# codec.net
KiCad netlist of a schematic drawn in Altium Designer
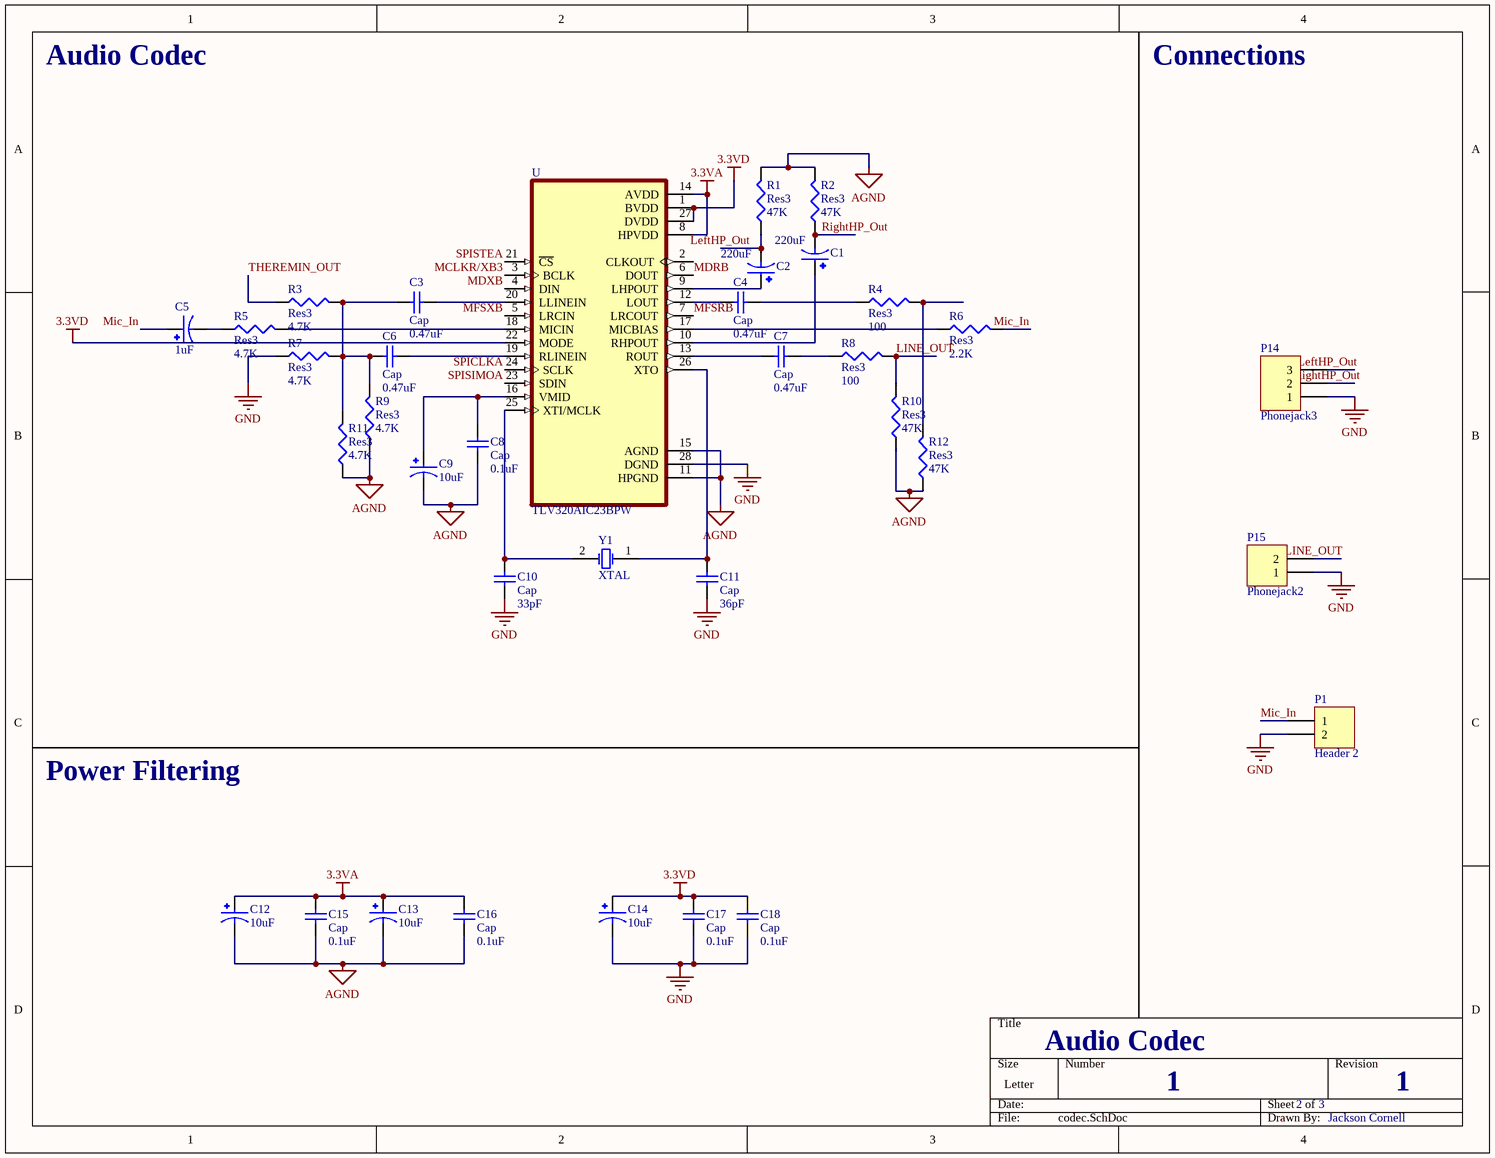
[diagram p0: codec.SchDoc]

(export (version "E")
  (design (tool "Eeschema 10.0.6"))
  (components
    (comp (ref "C1")
      (value "220uF")
      (footprint "CAPPRD500W60D1000H1250")
      (description "Aluminum Electrolytic Capacitors - Radial Leaded")
      (fields (field (name "MP") "EEU-FC1V221E") (field (name "MF") "Panasonic"))
      (libsource (lib "EEUFC1V221E") (part "EEUFC1V221E"))
    )
    (comp (ref "C2")
      (value "220uF")
      (footprint "CAPPRD500W60D1000H1250")
      (description "Aluminum Electrolytic Capacitors - Radial Leaded")
      (fields (field (name "MP") "EEU-FC1V221E") (field (name "MF") "Panasonic"))
      (libsource (lib "EEUFC1V221E") (part "EEUFC1V221E"))
    )
    (comp (ref "C3")
      (value "Cap")
      (footprint "Passives:CAPC0805")
      (description "Capacitor")
      (fields (field (name "ALTIUM_VALUE") "0.47uF") (field (name "PUBLISHER") "Altium Limited"))
      (libsource (lib "Miscellaneous Devices") (part "Cap"))
    )
    (comp (ref "C4")
      (value "Cap")
      (footprint "Passives:CAPC0805")
      (description "Capacitor")
      (fields (field (name "ALTIUM_VALUE") "0.47uF") (field (name "PUBLISHER") "Altium Limited"))
      (libsource (lib "Miscellaneous Devices") (part "Cap"))
    )
    (comp (ref "C5")
      (value "1uF")
      (footprint "CAPPRD500W60D1000H1250")
      (description "Aluminum Electrolytic Capacitors - Radial Leaded")
      (fields (field (name "MP") "EEU-FC1V221E") (field (name "MF") "Panasonic"))
      (libsource (lib "") (part "EEUFC1V221E_2"))
    )
    (comp (ref "C6")
      (value "Cap")
      (footprint "Passives:CAPC0805")
      (description "Capacitor")
      (fields (field (name "ALTIUM_VALUE") "0.47uF") (field (name "PUBLISHER") "Altium Limited"))
      (libsource (lib "Miscellaneous Devices") (part "Cap"))
    )
    (comp (ref "C7")
      (value "Cap")
      (footprint "Passives:CAPC0805")
      (description "Capacitor")
      (fields (field (name "ALTIUM_VALUE") "0.47uF") (field (name "PUBLISHER") "Altium Limited"))
      (libsource (lib "Miscellaneous Devices") (part "Cap"))
    )
    (comp (ref "C8")
      (value "Cap")
      (footprint "Passives:CAPC0805")
      (description "Capacitor")
      (fields (field (name "ALTIUM_VALUE") "0.1uF") (field (name "PUBLISHER") "Altium Limited"))
      (libsource (lib "Miscellaneous Devices") (part "Cap"))
    )
    (comp (ref "C9")
      (value "10uF")
      (footprint "CAPPRD500W60D1000H1250")
      (description "Aluminum Electrolytic Capacitors - Radial Leaded")
      (fields (field (name "MP") "EEU-FC1V221E") (field (name "MF") "Panasonic"))
      (libsource (lib "") (part "EEUFC1V221E_1"))
    )
    (comp (ref "C10")
      (value "Cap")
      (footprint "Passives:CAPC0805")
      (description "Capacitor")
      (fields (field (name "ALTIUM_VALUE") "33pF") (field (name "PUBLISHER") "Altium Limited"))
      (libsource (lib "Miscellaneous Devices") (part "Cap"))
    )
    (comp (ref "C11")
      (value "Cap")
      (footprint "Passives:CAPC0805")
      (description "Capacitor")
      (fields (field (name "ALTIUM_VALUE") "36pF") (field (name "PUBLISHER") "Altium Limited"))
      (libsource (lib "Miscellaneous Devices") (part "Cap"))
    )
    (comp (ref "C12")
      (value "10uF")
      (footprint "CAPPRD500W60D1000H1250")
      (description "Aluminum Electrolytic Capacitors - Radial Leaded")
      (fields (field (name "MP") "EEU-FC1V221E") (field (name "MF") "Panasonic"))
      (libsource (lib "") (part "EEUFC1V221E_1"))
    )
    (comp (ref "C13")
      (value "10uF")
      (footprint "CAPPRD500W60D1000H1250")
      (description "Aluminum Electrolytic Capacitors - Radial Leaded")
      (fields (field (name "MP") "EEU-FC1V221E") (field (name "MF") "Panasonic"))
      (libsource (lib "") (part "EEUFC1V221E_1"))
    )
    (comp (ref "C14")
      (value "10uF")
      (footprint "CAPPRD500W60D1000H1250")
      (description "Aluminum Electrolytic Capacitors - Radial Leaded")
      (fields (field (name "MP") "EEU-FC1V221E") (field (name "MF") "Panasonic"))
      (libsource (lib "") (part "EEUFC1V221E_1"))
    )
    (comp (ref "C15")
      (value "Cap")
      (footprint "Passives:CAPC0805")
      (description "Capacitor")
      (fields (field (name "ALTIUM_VALUE") "0.1uF") (field (name "PUBLISHER") "Altium Limited"))
      (libsource (lib "Miscellaneous Devices") (part "Cap"))
    )
    (comp (ref "C16")
      (value "Cap")
      (footprint "Passives:CAPC0805")
      (description "Capacitor")
      (fields (field (name "ALTIUM_VALUE") "0.1uF") (field (name "PUBLISHER") "Altium Limited"))
      (libsource (lib "Miscellaneous Devices") (part "Cap"))
    )
    (comp (ref "C17")
      (value "Cap")
      (footprint "Passives:CAPC0805")
      (description "Capacitor")
      (fields (field (name "ALTIUM_VALUE") "0.1uF") (field (name "PUBLISHER") "Altium Limited"))
      (libsource (lib "Miscellaneous Devices") (part "Cap"))
    )
    (comp (ref "C18")
      (value "Cap")
      (footprint "Passives:CAPC0805")
      (description "Capacitor")
      (fields (field (name "ALTIUM_VALUE") "0.1uF") (field (name "PUBLISHER") "Altium Limited"))
      (libsource (lib "Miscellaneous Devices") (part "Cap"))
    )
    (comp (ref "P1")
      (value "Header 2")
      (footprint "HDR1X2")
      (description "Header, 2-Pin")
      (fields (field (name "PUBLISHER") "Altium Limited"))
      (libsource (lib "Miscellaneous Connectors") (part "Header 2"))
    )
    (comp (ref "P14")
      (value "Phonejack3")
      (footprint "HDR1X3")
      (description "Header, 3-Pin")
      (fields (field (name "PUBLISHER") "Altium Limited"))
      (libsource (lib "Miscellaneous Connectors") (part "Header 3"))
    )
    (comp (ref "P15")
      (value "Phonejack2")
      (footprint "HDR1X2")
      (description "Header, 2-Pin")
      (fields (field (name "PUBLISHER") "Altium Limited"))
      (libsource (lib "") (part "Header 2_1"))
    )
    (comp (ref "R1")
      (value "Res3")
      (footprint "Passives:RES0805")
      (description "Resistor")
      (fields (field (name "ALTIUM_VALUE") "47K") (field (name "PUBLISHER") "Altium Limited"))
      (libsource (lib "Miscellaneous Devices") (part "Res3"))
    )
    (comp (ref "R2")
      (value "Res3")
      (footprint "Passives:RES0805")
      (description "Resistor")
      (fields (field (name "ALTIUM_VALUE") "47K") (field (name "PUBLISHER") "Altium Limited"))
      (libsource (lib "Miscellaneous Devices") (part "Res3"))
    )
    (comp (ref "R3")
      (value "Res3")
      (footprint "Passives:RES0805")
      (description "Resistor")
      (fields (field (name "ALTIUM_VALUE") "4.7K") (field (name "PUBLISHER") "Altium Limited"))
      (libsource (lib "Miscellaneous Devices") (part "Res3"))
    )
    (comp (ref "R4")
      (value "Res3")
      (footprint "Passives:RES0805")
      (description "Resistor")
      (fields (field (name "ALTIUM_VALUE") "100") (field (name "PUBLISHER") "Altium Limited"))
      (libsource (lib "Miscellaneous Devices") (part "Res3"))
    )
    (comp (ref "R5")
      (value "Res3")
      (footprint "Passives:RES0805")
      (description "Resistor")
      (fields (field (name "ALTIUM_VALUE") "4.7K") (field (name "PUBLISHER") "Altium Limited"))
      (libsource (lib "Miscellaneous Devices") (part "Res3"))
    )
    (comp (ref "R6")
      (value "Res3")
      (footprint "Passives:RES0805")
      (description "Resistor")
      (fields (field (name "ALTIUM_VALUE") "2.2K") (field (name "PUBLISHER") "Altium Limited"))
      (libsource (lib "Miscellaneous Devices") (part "Res3"))
    )
    (comp (ref "R7")
      (value "Res3")
      (footprint "Passives:RES0805")
      (description "Resistor")
      (fields (field (name "ALTIUM_VALUE") "4.7K") (field (name "PUBLISHER") "Altium Limited"))
      (libsource (lib "Miscellaneous Devices") (part "Res3"))
    )
    (comp (ref "R8")
      (value "Res3")
      (footprint "Passives:RES0805")
      (description "Resistor")
      (fields (field (name "ALTIUM_VALUE") "100") (field (name "PUBLISHER") "Altium Limited"))
      (libsource (lib "Miscellaneous Devices") (part "Res3"))
    )
    (comp (ref "R9")
      (value "Res3")
      (footprint "Passives:RES0805")
      (description "Resistor")
      (fields (field (name "ALTIUM_VALUE") "4.7K") (field (name "PUBLISHER") "Altium Limited"))
      (libsource (lib "Miscellaneous Devices") (part "Res3"))
    )
    (comp (ref "R10")
      (value "Res3")
      (footprint "Passives:RES0805")
      (description "Resistor")
      (fields (field (name "ALTIUM_VALUE") "47K") (field (name "PUBLISHER") "Altium Limited"))
      (libsource (lib "Miscellaneous Devices") (part "Res3"))
    )
    (comp (ref "R11")
      (value "Res3")
      (footprint "Passives:RES0805")
      (description "Resistor")
      (fields (field (name "ALTIUM_VALUE") "4.7K") (field (name "PUBLISHER") "Altium Limited"))
      (libsource (lib "Miscellaneous Devices") (part "Res3"))
    )
    (comp (ref "R12")
      (value "Res3")
      (footprint "Passives:RES0805")
      (description "Resistor")
      (fields (field (name "ALTIUM_VALUE") "47K") (field (name "PUBLISHER") "Altium Limited"))
      (libsource (lib "Miscellaneous Devices") (part "Res3"))
    )
    (comp (ref "U")
      (value "TLV320AIC23BPW")
      (footprint "SOP65P640X120-28N")
      (description "Low-Power Stereo CODEC with HP Amplifier 28-TSSOP -10 to 70")
      (fields (field (name "MF") "Texas Instruments"))
      (libsource (lib "TLV320AIC23BPW") (part "TLV320AIC23BPW"))
    )
    (comp (ref "Y1")
      (value "XTAL")
      (footprint "R38")
      (description "Crystal Oscillator")
      (fields (field (name "PUBLISHER") "Altium Limited"))
      (libsource (lib "Miscellaneous Devices") (part "XTAL"))
    )
  )
  (nets
    (net (code "1") (name "/LINE_OUT") (class "Default")
      (node (ref "P15") (pin "2") (pinfunction "2_2") (pintype "passive"))
      (node (ref "R10") (pin "2") (pinfunction "2_2") (pintype "passive"))
      (node (ref "R8") (pin "2") (pinfunction "2_2") (pintype "passive"))
    )
    (net (code "2") (name "/LeftHP_Out") (class "Default")
      (node (ref "C2") (pin "N") (pinfunction "N_N") (pintype "passive"))
      (node (ref "P14") (pin "3") (pinfunction "3_3") (pintype "passive"))
      (node (ref "R1") (pin "1") (pinfunction "1_1") (pintype "passive"))
    )
    (net (code "3") (name "/MCLKR{slash}XB3") (class "Default")
      (node (ref "U") (pin "3") (pinfunction "BCLK_3") (pintype "input"))
    )
    (net (code "4") (name "/MDRB") (class "Default")
      (node (ref "U") (pin "6") (pinfunction "DOUT_6") (pintype "output"))
    )
    (net (code "5") (name "/MDXB") (class "Default")
      (node (ref "U") (pin "4") (pinfunction "DIN_4") (pintype "input"))
    )
    (net (code "6") (name "/MFSRB") (class "Default")
      (node (ref "U") (pin "7") (pinfunction "LRCOUT_7") (pintype "output"))
    )
    (net (code "7") (name "/MFSXB") (class "Default")
      (node (ref "U") (pin "5") (pinfunction "LRCIN_5") (pintype "input"))
    )
    (net (code "8") (name "/Mic_In") (class "Default")
      (node (ref "C5") (pin "P") (pinfunction "P_P") (pintype "passive"))
      (node (ref "P1") (pin "1") (pinfunction "1_1") (pintype "passive"))
      (node (ref "R6") (pin "2") (pinfunction "2_2") (pintype "passive"))
    )
    (net (code "9") (name "/RightHP_Out") (class "Default")
      (node (ref "C1") (pin "N") (pinfunction "N_N") (pintype "passive"))
      (node (ref "P14") (pin "2") (pinfunction "2_2") (pintype "passive"))
      (node (ref "R2") (pin "1") (pinfunction "1_1") (pintype "passive"))
    )
    (net (code "10") (name "/SPICLKA") (class "Default")
      (node (ref "U") (pin "24") (pinfunction "SCLK_24") (pintype "input"))
    )
    (net (code "11") (name "/SPISIMOA") (class "Default")
      (node (ref "U") (pin "23") (pinfunction "SDIN_23") (pintype "input"))
    )
    (net (code "12") (name "/SPISTEA") (class "Default")
      (node (ref "U") (pin "21") (pinfunction "~{CS}_21") (pintype "input"))
    )
    (net (code "13") (name "/THEREMIN_OUT") (class "Default")
      (node (ref "R3") (pin "1") (pinfunction "1_1") (pintype "passive"))
    )
    (net (code "14") (name "3.3VA") (class "Default")
      (node (ref "C12") (pin "P") (pinfunction "P_P") (pintype "passive"))
      (node (ref "C13") (pin "P") (pinfunction "P_P") (pintype "passive"))
      (node (ref "C15") (pin "1") (pinfunction "1_1") (pintype "passive"))
      (node (ref "C16") (pin "1") (pinfunction "1_1") (pintype "passive"))
      (node (ref "U") (pin "14") (pinfunction "AVDD_14") (pintype "power_in"))
      (node (ref "U") (pin "8") (pinfunction "HPVDD_8") (pintype "power_in"))
    )
    (net (code "15") (name "3.3VD") (class "Default")
      (node (ref "C14") (pin "P") (pinfunction "P_P") (pintype "passive"))
      (node (ref "C17") (pin "2") (pinfunction "2_2") (pintype "passive"))
      (node (ref "C18") (pin "2") (pinfunction "2_2") (pintype "passive"))
      (node (ref "U") (pin "1") (pinfunction "BVDD_1") (pintype "power_in"))
      (node (ref "U") (pin "22") (pinfunction "MODE_22") (pintype "input"))
      (node (ref "U") (pin "27") (pinfunction "DVDD_27") (pintype "power_in"))
    )
    (net (code "16") (name "AGND") (class "Default")
      (node (ref "C12") (pin "N") (pinfunction "N_N") (pintype "passive"))
      (node (ref "C13") (pin "N") (pinfunction "N_N") (pintype "passive"))
      (node (ref "C15") (pin "2") (pinfunction "2_2") (pintype "passive"))
      (node (ref "C16") (pin "2") (pinfunction "2_2") (pintype "passive"))
      (node (ref "C8") (pin "1") (pinfunction "1_1") (pintype "passive"))
      (node (ref "C9") (pin "N") (pinfunction "N_N") (pintype "passive"))
      (node (ref "R1") (pin "2") (pinfunction "2_2") (pintype "passive"))
      (node (ref "R10") (pin "1") (pinfunction "1_1") (pintype "passive"))
      (node (ref "R11") (pin "1") (pinfunction "1_1") (pintype "passive"))
      (node (ref "R12") (pin "1") (pinfunction "1_1") (pintype "passive"))
      (node (ref "R2") (pin "2") (pinfunction "2_2") (pintype "passive"))
      (node (ref "R9") (pin "1") (pinfunction "1_1") (pintype "passive"))
      (node (ref "U") (pin "11") (pinfunction "HPGND_11") (pintype "power_in"))
      (node (ref "U") (pin "15") (pinfunction "AGND_15") (pintype "power_in"))
    )
    (net (code "17") (name "GND") (class "Default")
      (node (ref "C10") (pin "2") (pinfunction "2_2") (pintype "passive"))
      (node (ref "C11") (pin "2") (pinfunction "2_2") (pintype "passive"))
      (node (ref "C14") (pin "N") (pinfunction "N_N") (pintype "passive"))
      (node (ref "C17") (pin "1") (pinfunction "1_1") (pintype "passive"))
      (node (ref "C18") (pin "1") (pinfunction "1_1") (pintype "passive"))
      (node (ref "P1") (pin "2") (pinfunction "2_2") (pintype "passive"))
      (node (ref "P14") (pin "1") (pinfunction "1_1") (pintype "passive"))
      (node (ref "P15") (pin "1") (pinfunction "1_1") (pintype "passive"))
      (node (ref "R7") (pin "1") (pinfunction "1_1") (pintype "passive"))
      (node (ref "U") (pin "28") (pinfunction "DGND_28") (pintype "power_in"))
    )
    (net (code "18") (name "Net-(C3-Pad1)") (class "Default")
      (node (ref "C3") (pin "1") (pinfunction "1_1") (pintype "passive"))
      (node (ref "C6") (pin "1") (pinfunction "1_1") (pintype "passive"))
      (node (ref "R11") (pin "2") (pinfunction "2_2") (pintype "passive"))
      (node (ref "R3") (pin "2") (pinfunction "2_2") (pintype "passive"))
      (node (ref "R7") (pin "2") (pinfunction "2_2") (pintype "passive"))
      (node (ref "R9") (pin "2") (pinfunction "2_2") (pintype "passive"))
    )
    (net (code "19") (name "Net-(C4-Pad2)") (class "Default")
      (node (ref "C4") (pin "2") (pinfunction "2_2") (pintype "passive"))
      (node (ref "R4") (pin "1") (pinfunction "1_1") (pintype "passive"))
    )
    (net (code "20") (name "Net-(C5-PadN)") (class "Default")
      (node (ref "C5") (pin "N") (pinfunction "N_N") (pintype "passive"))
      (node (ref "R5") (pin "1") (pinfunction "1_1") (pintype "passive"))
    )
    (net (code "21") (name "Net-(C7-Pad2)") (class "Default")
      (node (ref "C7") (pin "2") (pinfunction "2_2") (pintype "passive"))
      (node (ref "R8") (pin "1") (pinfunction "1_1") (pintype "passive"))
    )
    (net (code "22") (name "Net-(R12-Pad2)") (class "Default")
      (node (ref "R12") (pin "2") (pinfunction "2_2") (pintype "passive"))
      (node (ref "R4") (pin "2") (pinfunction "2_2") (pintype "passive"))
    )
    (net (code "23") (name "Net-(U-LHPOUT)") (class "Default")
      (node (ref "C2") (pin "P") (pinfunction "P_P") (pintype "passive"))
      (node (ref "U") (pin "9") (pinfunction "LHPOUT_9") (pintype "output"))
    )
    (net (code "24") (name "Net-(U-LLINEIN)") (class "Default")
      (node (ref "C3") (pin "2") (pinfunction "2_2") (pintype "passive"))
      (node (ref "U") (pin "20") (pinfunction "LLINEIN_20") (pintype "input"))
    )
    (net (code "25") (name "Net-(U-LOUT)") (class "Default")
      (node (ref "C4") (pin "1") (pinfunction "1_1") (pintype "passive"))
      (node (ref "U") (pin "12") (pinfunction "LOUT_12") (pintype "output"))
    )
    (net (code "26") (name "Net-(U-MICBIAS)") (class "Default")
      (node (ref "R6") (pin "1") (pinfunction "1_1") (pintype "passive"))
      (node (ref "U") (pin "17") (pinfunction "MICBIAS_17") (pintype "output"))
    )
    (net (code "27") (name "Net-(U-MICIN)") (class "Default")
      (node (ref "R5") (pin "2") (pinfunction "2_2") (pintype "passive"))
      (node (ref "U") (pin "18") (pinfunction "MICIN_18") (pintype "input"))
    )
    (net (code "28") (name "Net-(U-RHPOUT)") (class "Default")
      (node (ref "C1") (pin "P") (pinfunction "P_P") (pintype "passive"))
      (node (ref "U") (pin "10") (pinfunction "RHPOUT_10") (pintype "output"))
    )
    (net (code "29") (name "Net-(U-RLINEIN)") (class "Default")
      (node (ref "C6") (pin "2") (pinfunction "2_2") (pintype "passive"))
      (node (ref "U") (pin "19") (pinfunction "RLINEIN_19") (pintype "input"))
    )
    (net (code "30") (name "Net-(U-ROUT)") (class "Default")
      (node (ref "C7") (pin "1") (pinfunction "1_1") (pintype "passive"))
      (node (ref "U") (pin "13") (pinfunction "ROUT_13") (pintype "output"))
    )
    (net (code "31") (name "Net-(U-VMID)") (class "Default")
      (node (ref "C8") (pin "2") (pinfunction "2_2") (pintype "passive"))
      (node (ref "C9") (pin "P") (pinfunction "P_P") (pintype "passive"))
      (node (ref "U") (pin "16") (pinfunction "VMID_16") (pintype "input"))
    )
    (net (code "32") (name "Net-(U-XTI{slash}MCLK)") (class "Default")
      (node (ref "C10") (pin "1") (pinfunction "1_1") (pintype "passive"))
      (node (ref "U") (pin "25") (pinfunction "XTI/MCLK_25") (pintype "input"))
      (node (ref "Y1") (pin "2") (pinfunction "OSC2_2") (pintype "passive"))
    )
    (net (code "33") (name "Net-(U-XTO)") (class "Default")
      (node (ref "C11") (pin "1") (pinfunction "1_1") (pintype "passive"))
      (node (ref "U") (pin "26") (pinfunction "XTO_26") (pintype "output"))
      (node (ref "Y1") (pin "1") (pinfunction "OSC1_1") (pintype "passive"))
    )
    (net (code "34") (name "unconnected-(U-CLKOUT-Pad2)") (class "Default")
      (node (ref "U") (pin "2") (pinfunction "CLKOUT_2") (pintype "output"))
    )
  )
)
